# FubarStep_v13.net
KiCad netlist of a schematic drawn in EAGLE
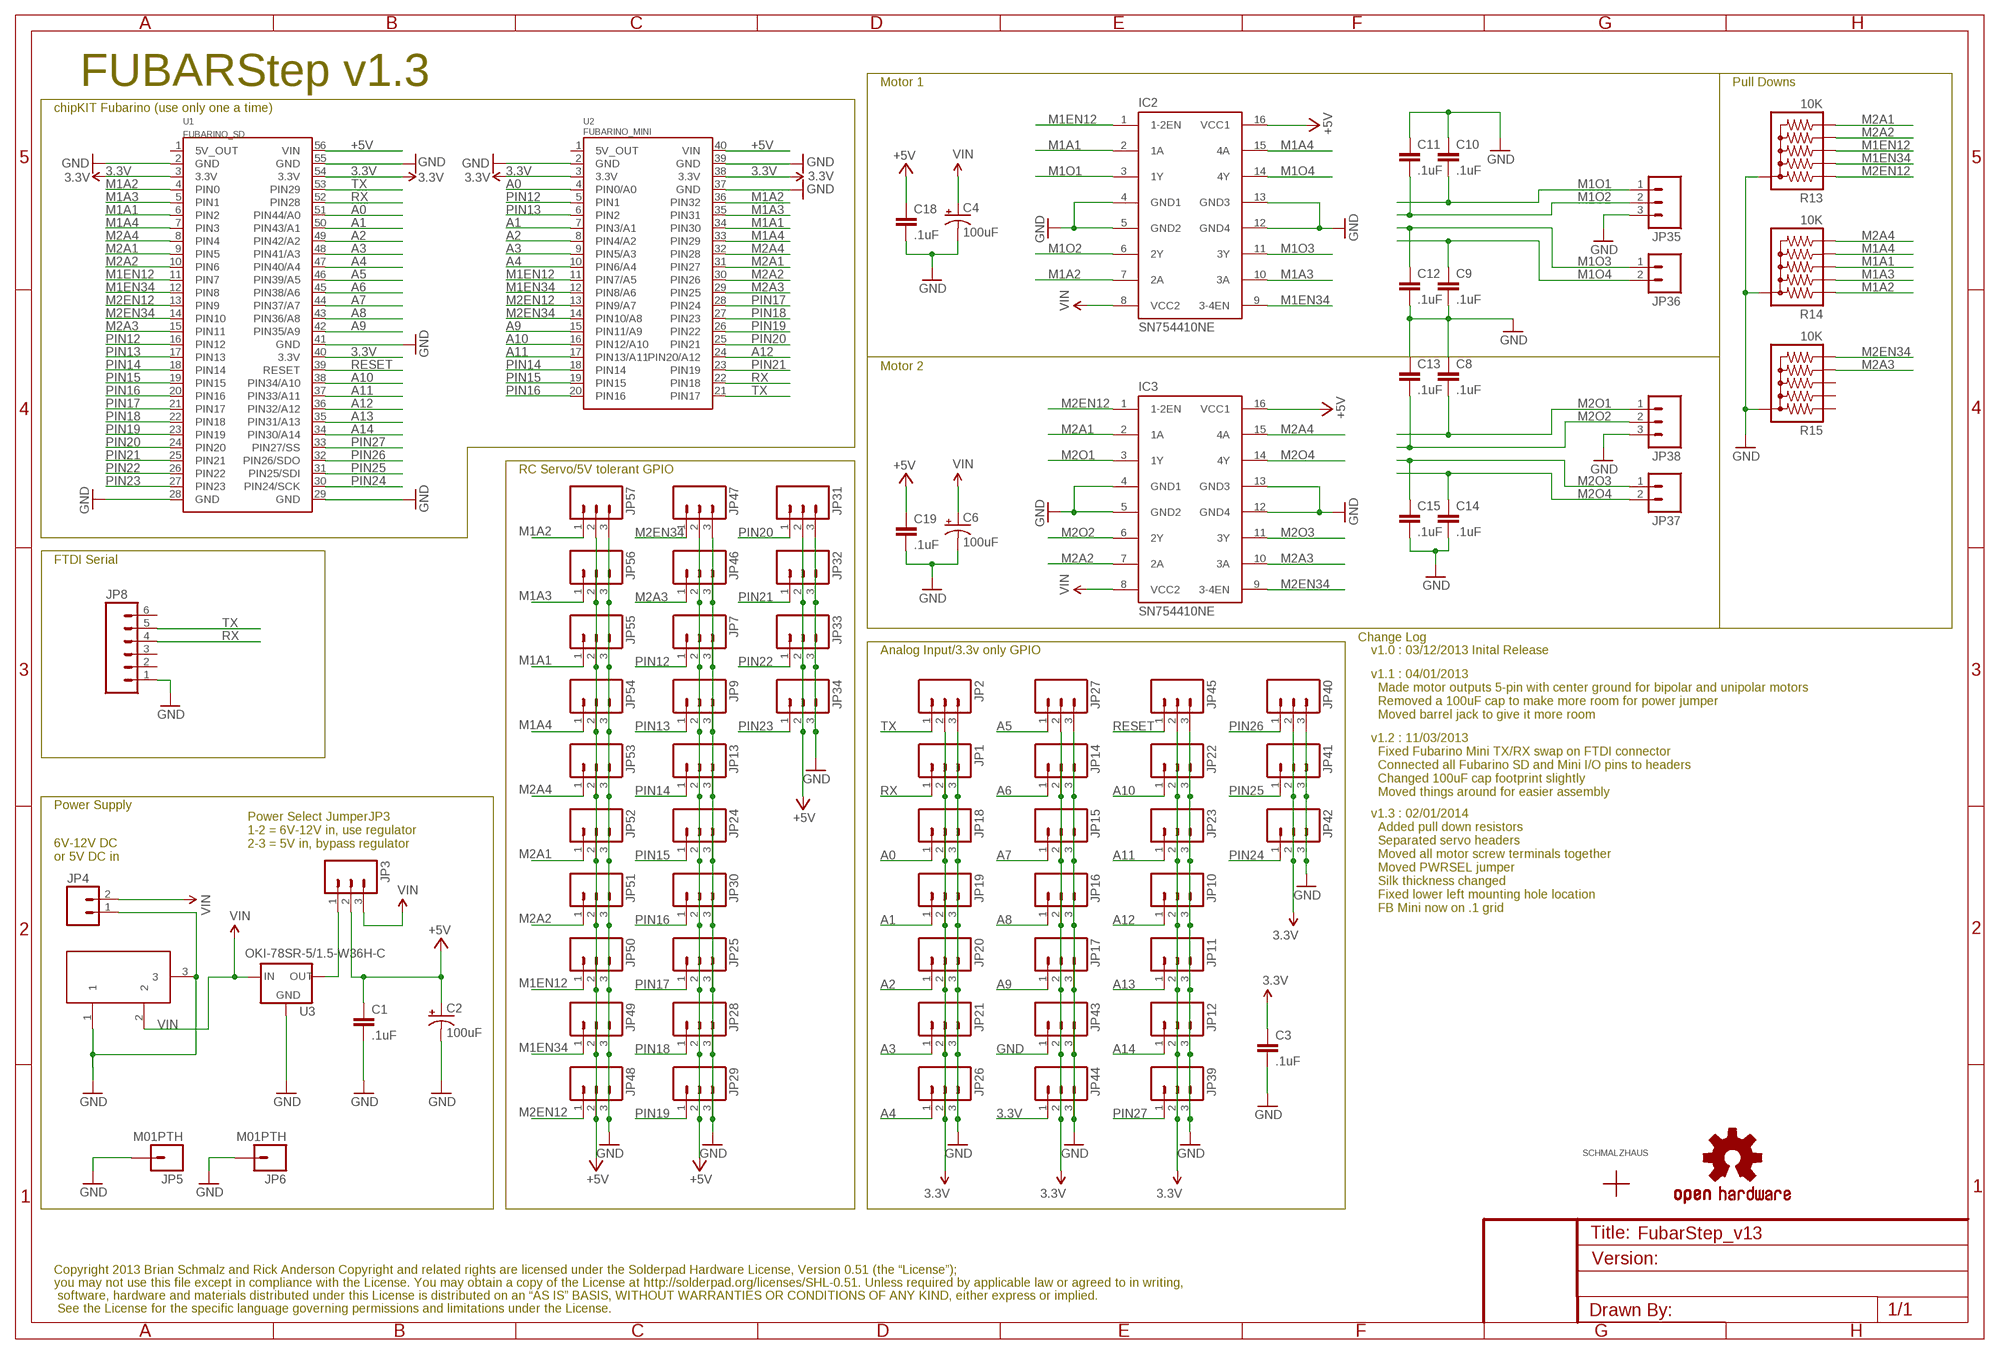
[diagram p0: schematic, sheet 1]

(export (version "E")
  (design (tool "Eeschema 10.0.6"))
  (components
    (comp (ref "C1")
      (value ".1uF")
      (footprint "eagle-import:CAP-PTH-SMALL")
      (libsource (lib "eagle-import") (part "CAPPTH"))
    )
    (comp (ref "C2")
      (value "100uF")
      (footprint "eagle-import:CPOL-RADIAL-100UF")
      (libsource (lib "eagle-import") (part "CAP_ELECTROLYTICPTH1_BPS"))
    )
    (comp (ref "C3")
      (value ".1uF")
      (footprint "eagle-import:CAP-PTH-SMALL")
      (libsource (lib "eagle-import") (part "CAPPTH"))
    )
    (comp (ref "C4")
      (value "100uF")
      (footprint "eagle-import:CPOL-RADIAL-100UF")
      (libsource (lib "eagle-import") (part "CAP_ELECTROLYTICPTH1_BPS"))
    )
    (comp (ref "C6")
      (value "100uF")
      (footprint "eagle-import:CPOL-RADIAL-100UF")
      (libsource (lib "eagle-import") (part "CAP_ELECTROLYTICPTH1_BPS"))
    )
    (comp (ref "C8")
      (value ".1uF")
      (footprint "eagle-import:CAP-PTH-SMALL")
      (libsource (lib "eagle-import") (part "CAPPTH"))
    )
    (comp (ref "C9")
      (value ".1uF")
      (footprint "eagle-import:CAP-PTH-SMALL")
      (libsource (lib "eagle-import") (part "CAPPTH"))
    )
    (comp (ref "C10")
      (value ".1uF")
      (footprint "eagle-import:CAP-PTH-SMALL")
      (libsource (lib "eagle-import") (part "CAPPTH"))
    )
    (comp (ref "C11")
      (value ".1uF")
      (footprint "eagle-import:CAP-PTH-SMALL")
      (libsource (lib "eagle-import") (part "CAPPTH"))
    )
    (comp (ref "C12")
      (value ".1uF")
      (footprint "eagle-import:CAP-PTH-SMALL")
      (libsource (lib "eagle-import") (part "CAPPTH"))
    )
    (comp (ref "C13")
      (value ".1uF")
      (footprint "eagle-import:CAP-PTH-SMALL")
      (libsource (lib "eagle-import") (part "CAPPTH"))
    )
    (comp (ref "C14")
      (value ".1uF")
      (footprint "eagle-import:CAP-PTH-SMALL")
      (libsource (lib "eagle-import") (part "CAPPTH"))
    )
    (comp (ref "C15")
      (value ".1uF")
      (footprint "eagle-import:CAP-PTH-SMALL")
      (libsource (lib "eagle-import") (part "CAPPTH"))
    )
    (comp (ref "C18")
      (value ".1uF")
      (footprint "eagle-import:CAP-PTH-SMALL")
      (libsource (lib "eagle-import") (part "CAPPTH"))
    )
    (comp (ref "C19")
      (value ".1uF")
      (footprint "eagle-import:CAP-PTH-SMALL")
      (libsource (lib "eagle-import") (part "CAPPTH"))
    )
    (comp (ref "IC2")
      (value "SN754410NE")
      (footprint "eagle-import:DIL16")
      (fields (field (name "MF") "Arrow Electronics") (field (name "MPN") "L293E"))
      (libsource (lib "eagle-import") (part "L293E"))
    )
    (comp (ref "IC3")
      (value "SN754410NE")
      (footprint "eagle-import:DIL16")
      (fields (field (name "MF") "Arrow Electronics") (field (name "MPN") "L293E"))
      (libsource (lib "eagle-import") (part "L293E"))
    )
    (comp (ref "JP1")
      (value "M03PTH")
      (footprint "eagle-import:1X03")
      (libsource (lib "eagle-import") (part "M03PTH"))
    )
    (comp (ref "JP2")
      (value "M03PTH")
      (footprint "eagle-import:1X03")
      (libsource (lib "eagle-import") (part "M03PTH"))
    )
    (comp (ref "JP3")
      (value "M03PTH")
      (footprint "eagle-import:1X03")
      (libsource (lib "eagle-import") (part "M03PTH"))
    )
    (comp (ref "JP4")
      (value "M023.5MM")
      (footprint "eagle-import:SCREWTERMINAL-3.5MM-2")
      (libsource (lib "eagle-import") (part "M023.5MM"))
    )
    (comp (ref "JP5")
      (value "M01PTH")
      (footprint "eagle-import:1X01")
      (libsource (lib "eagle-import") (part "M01PTH"))
    )
    (comp (ref "JP6")
      (value "M01PTH")
      (footprint "eagle-import:1X01")
      (libsource (lib "eagle-import") (part "M01PTH"))
    )
    (comp (ref "JP7")
      (value "M03PTH")
      (footprint "eagle-import:1X03")
      (libsource (lib "eagle-import") (part "M03PTH"))
    )
    (comp (ref "JP8")
      (value "M06LOCK")
      (footprint "eagle-import:1X06_LOCK")
      (libsource (lib "eagle-import") (part "M06LOCK"))
    )
    (comp (ref "JP9")
      (value "M03PTH")
      (footprint "eagle-import:1X03")
      (libsource (lib "eagle-import") (part "M03PTH"))
    )
    (comp (ref "JP10")
      (value "M03PTH")
      (footprint "eagle-import:1X03")
      (libsource (lib "eagle-import") (part "M03PTH"))
    )
    (comp (ref "JP11")
      (value "M03PTH")
      (footprint "eagle-import:1X03")
      (libsource (lib "eagle-import") (part "M03PTH"))
    )
    (comp (ref "JP12")
      (value "M03PTH")
      (footprint "eagle-import:1X03")
      (libsource (lib "eagle-import") (part "M03PTH"))
    )
    (comp (ref "JP13")
      (value "M03PTH")
      (footprint "eagle-import:1X03")
      (libsource (lib "eagle-import") (part "M03PTH"))
    )
    (comp (ref "JP14")
      (value "M03PTH")
      (footprint "eagle-import:1X03")
      (libsource (lib "eagle-import") (part "M03PTH"))
    )
    (comp (ref "JP15")
      (value "M03PTH")
      (footprint "eagle-import:1X03")
      (libsource (lib "eagle-import") (part "M03PTH"))
    )
    (comp (ref "JP16")
      (value "M03PTH")
      (footprint "eagle-import:1X03")
      (libsource (lib "eagle-import") (part "M03PTH"))
    )
    (comp (ref "JP17")
      (value "M03PTH")
      (footprint "eagle-import:1X03")
      (libsource (lib "eagle-import") (part "M03PTH"))
    )
    (comp (ref "JP18")
      (value "M03PTH")
      (footprint "eagle-import:1X03")
      (libsource (lib "eagle-import") (part "M03PTH"))
    )
    (comp (ref "JP19")
      (value "M03PTH")
      (footprint "eagle-import:1X03")
      (libsource (lib "eagle-import") (part "M03PTH"))
    )
    (comp (ref "JP20")
      (value "M03PTH")
      (footprint "eagle-import:1X03")
      (libsource (lib "eagle-import") (part "M03PTH"))
    )
    (comp (ref "JP21")
      (value "M03PTH")
      (footprint "eagle-import:1X03")
      (libsource (lib "eagle-import") (part "M03PTH"))
    )
    (comp (ref "JP22")
      (value "M03PTH")
      (footprint "eagle-import:1X03")
      (libsource (lib "eagle-import") (part "M03PTH"))
    )
    (comp (ref "JP23")
      (value "M03PTH")
      (footprint "eagle-import:1X03")
      (libsource (lib "eagle-import") (part "M03PTH"))
    )
    (comp (ref "JP24")
      (value "M03PTH")
      (footprint "eagle-import:1X03")
      (libsource (lib "eagle-import") (part "M03PTH"))
    )
    (comp (ref "JP25")
      (value "M03PTH")
      (footprint "eagle-import:1X03")
      (libsource (lib "eagle-import") (part "M03PTH"))
    )
    (comp (ref "JP26")
      (value "M03PTH")
      (footprint "eagle-import:1X03")
      (libsource (lib "eagle-import") (part "M03PTH"))
    )
    (comp (ref "JP27")
      (value "M03PTH")
      (footprint "eagle-import:1X03")
      (libsource (lib "eagle-import") (part "M03PTH"))
    )
    (comp (ref "JP28")
      (value "M03PTH")
      (footprint "eagle-import:1X03")
      (libsource (lib "eagle-import") (part "M03PTH"))
    )
    (comp (ref "JP29")
      (value "M03PTH")
      (footprint "eagle-import:1X03")
      (libsource (lib "eagle-import") (part "M03PTH"))
    )
    (comp (ref "JP30")
      (value "M03PTH")
      (footprint "eagle-import:1X03")
      (libsource (lib "eagle-import") (part "M03PTH"))
    )
    (comp (ref "JP31")
      (value "M03PTH")
      (footprint "eagle-import:1X03")
      (libsource (lib "eagle-import") (part "M03PTH"))
    )
    (comp (ref "JP32")
      (value "M03PTH")
      (footprint "eagle-import:1X03")
      (libsource (lib "eagle-import") (part "M03PTH"))
    )
    (comp (ref "JP33")
      (value "M03PTH")
      (footprint "eagle-import:1X03")
      (libsource (lib "eagle-import") (part "M03PTH"))
    )
    (comp (ref "JP34")
      (value "M03PTH")
      (footprint "eagle-import:1X03")
      (libsource (lib "eagle-import") (part "M03PTH"))
    )
    (comp (ref "JP35")
      (value "M03SCREW")
      (footprint "eagle-import:SCREWTERMINAL-3.5MM-3")
      (libsource (lib "eagle-import") (part "M03SCREW"))
    )
    (comp (ref "JP36")
      (value "M023.5MM")
      (footprint "eagle-import:SCREWTERMINAL-3.5MM-2")
      (libsource (lib "eagle-import") (part "M023.5MM"))
    )
    (comp (ref "JP37")
      (value "M023.5MM")
      (footprint "eagle-import:SCREWTERMINAL-3.5MM-2")
      (libsource (lib "eagle-import") (part "M023.5MM"))
    )
    (comp (ref "JP38")
      (value "M03SCREW")
      (footprint "eagle-import:SCREWTERMINAL-3.5MM-3")
      (libsource (lib "eagle-import") (part "M03SCREW"))
    )
    (comp (ref "JP39")
      (value "M03PTH")
      (footprint "eagle-import:1X03")
      (libsource (lib "eagle-import") (part "M03PTH"))
    )
    (comp (ref "JP40")
      (value "M03PTH")
      (footprint "eagle-import:1X03")
      (libsource (lib "eagle-import") (part "M03PTH"))
    )
    (comp (ref "JP41")
      (value "M03PTH")
      (footprint "eagle-import:1X03")
      (libsource (lib "eagle-import") (part "M03PTH"))
    )
    (comp (ref "JP42")
      (value "M03PTH")
      (footprint "eagle-import:1X03")
      (libsource (lib "eagle-import") (part "M03PTH"))
    )
    (comp (ref "JP43")
      (value "M03PTH")
      (footprint "eagle-import:1X03")
      (libsource (lib "eagle-import") (part "M03PTH"))
    )
    (comp (ref "JP44")
      (value "M03PTH")
      (footprint "eagle-import:1X03")
      (libsource (lib "eagle-import") (part "M03PTH"))
    )
    (comp (ref "JP45")
      (value "M03PTH")
      (footprint "eagle-import:1X03")
      (libsource (lib "eagle-import") (part "M03PTH"))
    )
    (comp (ref "JP46")
      (value "M03PTH")
      (footprint "eagle-import:1X03")
      (libsource (lib "eagle-import") (part "M03PTH"))
    )
    (comp (ref "JP47")
      (value "M03PTH")
      (footprint "eagle-import:1X03")
      (libsource (lib "eagle-import") (part "M03PTH"))
    )
    (comp (ref "JP48")
      (value "M03PTH")
      (footprint "eagle-import:1X03")
      (libsource (lib "eagle-import") (part "M03PTH"))
    )
    (comp (ref "JP49")
      (value "M03PTH")
      (footprint "eagle-import:1X03")
      (libsource (lib "eagle-import") (part "M03PTH"))
    )
    (comp (ref "JP50")
      (value "M03PTH")
      (footprint "eagle-import:1X03")
      (libsource (lib "eagle-import") (part "M03PTH"))
    )
    (comp (ref "JP51")
      (value "M03PTH")
      (footprint "eagle-import:1X03")
      (libsource (lib "eagle-import") (part "M03PTH"))
    )
    (comp (ref "JP52")
      (value "M03PTH")
      (footprint "eagle-import:1X03")
      (libsource (lib "eagle-import") (part "M03PTH"))
    )
    (comp (ref "JP53")
      (value "M03PTH")
      (footprint "eagle-import:1X03")
      (libsource (lib "eagle-import") (part "M03PTH"))
    )
    (comp (ref "JP54")
      (value "M03PTH")
      (footprint "eagle-import:1X03")
      (libsource (lib "eagle-import") (part "M03PTH"))
    )
    (comp (ref "JP55")
      (value "M03PTH")
      (footprint "eagle-import:1X03")
      (libsource (lib "eagle-import") (part "M03PTH"))
    )
    (comp (ref "JP56")
      (value "M03PTH")
      (footprint "eagle-import:1X03")
      (libsource (lib "eagle-import") (part "M03PTH"))
    )
    (comp (ref "JP57")
      (value "M03PTH")
      (footprint "eagle-import:1X03")
      (libsource (lib "eagle-import") (part "M03PTH"))
    )
    (comp (ref "LOGO1")
      (value "OSHW-LOGOM")
      (footprint "eagle-import:OSHW-LOGO-M")
      (libsource (lib "eagle-import") (part "OSHW-LOGOM"))
    )
    (comp (ref "R13")
      (value "10K")
      (footprint "eagle-import:RPACK-SIP-PTH-5")
      (libsource (lib "eagle-import") (part "RPACK-BUSSED-SIP-PTH-5"))
    )
    (comp (ref "R14")
      (value "10K")
      (footprint "eagle-import:RPACK-SIP-PTH-5")
      (libsource (lib "eagle-import") (part "RPACK-BUSSED-SIP-PTH-5"))
    )
    (comp (ref "R15")
      (value "10K")
      (footprint "eagle-import:RPACK-SIP-PTH-5")
      (libsource (lib "eagle-import") (part "RPACK-BUSSED-SIP-PTH-5"))
    )
    (comp (ref "U$1")
      (value "SCHMALZHAUSSCHMALZHAUS_SMALL")
      (footprint "eagle-import:SCHMALZHAUS_SMALL")
      (libsource (lib "eagle-import") (part "SCHMALZHAUSSCHMALZHAUS_SMALL"))
    )
    (comp (ref "U1")
      (value "FUBARINO_SD")
      (footprint "eagle-import:FUBARINO_SD")
      (libsource (lib "eagle-import") (part "FUBARINO_SD"))
    )
    (comp (ref "U2")
      (value "FUBARINO_MINI")
      (footprint "eagle-import:FUBARINO_MINI")
      (libsource (lib "eagle-import") (part "FUBARINO_MINI"))
    )
    (comp (ref "U3")
      (value "OKI-78SR-5/1.5-W36H-C")
      (footprint "eagle-import:TO220-IGO")
      (libsource (lib "eagle-import") (part "V_REG_78XXSINK"))
    )
    (comp (ref "X1")
      (value "DC21MMX")
      (footprint "eagle-import:DC-21MM")
      (libsource (lib "eagle-import") (part "DC21MMX"))
    )
  )
  (nets
    (net (code "1") (name "+5V") (class "Default")
      (node (ref "C1") (pin "1") (pinfunction "1_1") (pintype "passive"))
      (node (ref "C18") (pin "1") (pinfunction "1_1") (pintype "passive"))
      (node (ref "C19") (pin "1") (pinfunction "1_1") (pintype "passive"))
      (node (ref "C2") (pin "1") (pinfunction "+_1") (pintype "passive"))
      (node (ref "IC2") (pin "16") (pinfunction "VCC1_16") (pintype "power_in"))
      (node (ref "IC3") (pin "16") (pinfunction "VCC1_16") (pintype "power_in"))
      (node (ref "JP13") (pin "2") (pinfunction "2_2") (pintype "passive"))
      (node (ref "JP24") (pin "2") (pinfunction "2_2") (pintype "passive"))
      (node (ref "JP25") (pin "2") (pinfunction "2_2") (pintype "passive"))
      (node (ref "JP28") (pin "2") (pinfunction "2_2") (pintype "passive"))
      (node (ref "JP29") (pin "2") (pinfunction "2_2") (pintype "passive"))
      (node (ref "JP3") (pin "2") (pinfunction "2_2") (pintype "passive"))
      (node (ref "JP30") (pin "2") (pinfunction "2_2") (pintype "passive"))
      (node (ref "JP31") (pin "2") (pinfunction "2_2") (pintype "passive"))
      (node (ref "JP32") (pin "2") (pinfunction "2_2") (pintype "passive"))
      (node (ref "JP33") (pin "2") (pinfunction "2_2") (pintype "passive"))
      (node (ref "JP34") (pin "2") (pinfunction "2_2") (pintype "passive"))
      (node (ref "JP46") (pin "2") (pinfunction "2_2") (pintype "passive"))
      (node (ref "JP47") (pin "2") (pinfunction "2_2") (pintype "passive"))
      (node (ref "JP48") (pin "2") (pinfunction "2_2") (pintype "passive"))
      (node (ref "JP49") (pin "2") (pinfunction "2_2") (pintype "passive"))
      (node (ref "JP50") (pin "2") (pinfunction "2_2") (pintype "passive"))
      (node (ref "JP51") (pin "2") (pinfunction "2_2") (pintype "passive"))
      (node (ref "JP52") (pin "2") (pinfunction "2_2") (pintype "passive"))
      (node (ref "JP53") (pin "2") (pinfunction "2_2") (pintype "passive"))
      (node (ref "JP54") (pin "2") (pinfunction "2_2") (pintype "passive"))
      (node (ref "JP55") (pin "2") (pinfunction "2_2") (pintype "passive"))
      (node (ref "JP56") (pin "2") (pinfunction "2_2") (pintype "passive"))
      (node (ref "JP57") (pin "2") (pinfunction "2_2") (pintype "passive"))
      (node (ref "JP7") (pin "2") (pinfunction "2_2") (pintype "passive"))
      (node (ref "JP9") (pin "2") (pinfunction "2_2") (pintype "passive"))
      (node (ref "U1") (pin "56") (pinfunction "VIN_56") (pintype "bidirectional"))
      (node (ref "U2") (pin "40") (pinfunction "VIN_40") (pintype "bidirectional"))
    )
    (net (code "2") (name "/A0") (class "Default")
      (node (ref "JP18") (pin "1") (pinfunction "1_1") (pintype "passive"))
      (node (ref "U1") (pin "51") (pinfunction "PIN44/A0_51") (pintype "bidirectional"))
      (node (ref "U2") (pin "4") (pinfunction "PIN0/A0_4") (pintype "bidirectional"))
    )
    (net (code "3") (name "/A1") (class "Default")
      (node (ref "JP19") (pin "1") (pinfunction "1_1") (pintype "passive"))
      (node (ref "U1") (pin "50") (pinfunction "PIN43/A1_50") (pintype "bidirectional"))
      (node (ref "U2") (pin "7") (pinfunction "PIN3/A1_7") (pintype "bidirectional"))
    )
    (net (code "4") (name "/A2") (class "Default")
      (node (ref "JP20") (pin "1") (pinfunction "1_1") (pintype "passive"))
      (node (ref "U1") (pin "49") (pinfunction "PIN42/A2_49") (pintype "bidirectional"))
      (node (ref "U2") (pin "8") (pinfunction "PIN4/A2_8") (pintype "bidirectional"))
    )
    (net (code "5") (name "/A3") (class "Default")
      (node (ref "JP21") (pin "1") (pinfunction "1_1") (pintype "passive"))
      (node (ref "U1") (pin "48") (pinfunction "PIN41/A3_48") (pintype "bidirectional"))
      (node (ref "U2") (pin "9") (pinfunction "PIN5/A3_9") (pintype "bidirectional"))
    )
    (net (code "6") (name "/A4") (class "Default")
      (node (ref "JP26") (pin "1") (pinfunction "1_1") (pintype "passive"))
      (node (ref "U1") (pin "47") (pinfunction "PIN40/A4_47") (pintype "bidirectional"))
      (node (ref "U2") (pin "10") (pinfunction "PIN6/A4_10") (pintype "bidirectional"))
    )
    (net (code "7") (name "/A5") (class "Default")
      (node (ref "JP27") (pin "1") (pinfunction "1_1") (pintype "passive"))
      (node (ref "U1") (pin "46") (pinfunction "PIN39/A5_46") (pintype "bidirectional"))
    )
    (net (code "8") (name "/A6") (class "Default")
      (node (ref "JP14") (pin "1") (pinfunction "1_1") (pintype "passive"))
      (node (ref "U1") (pin "45") (pinfunction "PIN38/A6_45") (pintype "bidirectional"))
    )
    (net (code "9") (name "/A7") (class "Default")
      (node (ref "JP15") (pin "1") (pinfunction "1_1") (pintype "passive"))
      (node (ref "U1") (pin "44") (pinfunction "PIN37/A7_44") (pintype "bidirectional"))
    )
    (net (code "10") (name "/A8") (class "Default")
      (node (ref "JP16") (pin "1") (pinfunction "1_1") (pintype "passive"))
      (node (ref "U1") (pin "43") (pinfunction "PIN36/A8_43") (pintype "bidirectional"))
    )
    (net (code "11") (name "/A9") (class "Default")
      (node (ref "JP17") (pin "1") (pinfunction "1_1") (pintype "passive"))
      (node (ref "U1") (pin "42") (pinfunction "PIN35/A9_42") (pintype "bidirectional"))
      (node (ref "U2") (pin "15") (pinfunction "PIN11/A9_15") (pintype "bidirectional"))
    )
    (net (code "12") (name "/A10") (class "Default")
      (node (ref "JP22") (pin "1") (pinfunction "1_1") (pintype "passive"))
      (node (ref "U1") (pin "38") (pinfunction "PIN34/A10_38") (pintype "bidirectional"))
      (node (ref "U2") (pin "16") (pinfunction "PIN12/A10_16") (pintype "bidirectional"))
    )
    (net (code "13") (name "/A11") (class "Default")
      (node (ref "JP23") (pin "1") (pinfunction "1_1") (pintype "passive"))
      (node (ref "U1") (pin "37") (pinfunction "PIN33/A11_37") (pintype "bidirectional"))
      (node (ref "U2") (pin "17") (pinfunction "PIN13/A11_17") (pintype "bidirectional"))
    )
    (net (code "14") (name "/A12") (class "Default")
      (node (ref "JP10") (pin "1") (pinfunction "1_1") (pintype "passive"))
      (node (ref "U1") (pin "36") (pinfunction "PIN32/A12_36") (pintype "bidirectional"))
      (node (ref "U2") (pin "24") (pinfunction "PIN20/A12_24") (pintype "bidirectional"))
    )
    (net (code "15") (name "/A13") (class "Default")
      (node (ref "JP11") (pin "1") (pinfunction "1_1") (pintype "passive"))
      (node (ref "U1") (pin "35") (pinfunction "PIN31/A13_35") (pintype "bidirectional"))
    )
    (net (code "16") (name "/A14") (class "Default")
      (node (ref "JP12") (pin "1") (pinfunction "1_1") (pintype "passive"))
      (node (ref "U1") (pin "34") (pinfunction "PIN30/A14_34") (pintype "bidirectional"))
    )
    (net (code "17") (name "/M1A1") (class "Default")
      (node (ref "IC2") (pin "2") (pinfunction "1A_2") (pintype "input"))
      (node (ref "JP55") (pin "1") (pinfunction "1_1") (pintype "passive"))
      (node (ref "R14") (pin "P$4") (pinfunction "4_P$4") (pintype "passive"))
      (node (ref "U1") (pin "6") (pinfunction "PIN2_6") (pintype "bidirectional"))
      (node (ref "U2") (pin "34") (pinfunction "PIN30_34") (pintype "bidirectional"))
    )
    (net (code "18") (name "/M1A2") (class "Default")
      (node (ref "IC2") (pin "7") (pinfunction "2A_7") (pintype "input"))
      (node (ref "JP57") (pin "1") (pinfunction "1_1") (pintype "passive"))
      (node (ref "R14") (pin "P$2") (pinfunction "2_P$2") (pintype "passive"))
      (node (ref "U1") (pin "4") (pinfunction "PIN0_4") (pintype "bidirectional"))
      (node (ref "U2") (pin "36") (pinfunction "PIN32_36") (pintype "bidirectional"))
    )
    (net (code "19") (name "/M1A3") (class "Default")
      (node (ref "IC2") (pin "10") (pinfunction "3A_10") (pintype "input"))
      (node (ref "JP56") (pin "1") (pinfunction "1_1") (pintype "passive"))
      (node (ref "R14") (pin "P$3") (pinfunction "3_P$3") (pintype "passive"))
      (node (ref "U1") (pin "5") (pinfunction "PIN1_5") (pintype "bidirectional"))
      (node (ref "U2") (pin "35") (pinfunction "PIN31_35") (pintype "bidirectional"))
    )
    (net (code "20") (name "/M1A4") (class "Default")
      (node (ref "IC2") (pin "15") (pinfunction "4A_15") (pintype "input"))
      (node (ref "JP54") (pin "1") (pinfunction "1_1") (pintype "passive"))
      (node (ref "R14") (pin "P$5") (pinfunction "5_P$5") (pintype "passive"))
      (node (ref "U1") (pin "7") (pinfunction "PIN3_7") (pintype "bidirectional"))
      (node (ref "U2") (pin "33") (pinfunction "PIN29_33") (pintype "bidirectional"))
    )
    (net (code "21") (name "/M1EN12") (class "Default")
      (node (ref "IC2") (pin "1") (pinfunction "1-2EN_1") (pintype "input"))
      (node (ref "JP50") (pin "1") (pinfunction "1_1") (pintype "passive"))
      (node (ref "R13") (pin "P$4") (pinfunction "4_P$4") (pintype "passive"))
      (node (ref "U1") (pin "11") (pinfunction "PIN7_11") (pintype "bidirectional"))
      (node (ref "U2") (pin "11") (pinfunction "PIN7/A5_11") (pintype "bidirectional"))
    )
    (net (code "22") (name "/M1EN34") (class "Default")
      (node (ref "IC2") (pin "9") (pinfunction "3-4EN_9") (pintype "input"))
      (node (ref "JP49") (pin "1") (pinfunction "1_1") (pintype "passive"))
      (node (ref "R13") (pin "P$3") (pinfunction "3_P$3") (pintype "passive"))
      (node (ref "U1") (pin "12") (pinfunction "PIN8_12") (pintype "bidirectional"))
      (node (ref "U2") (pin "12") (pinfunction "PIN8/A6_12") (pintype "bidirectional"))
    )
    (net (code "23") (name "/M1O1") (class "Default")
      (node (ref "C10") (pin "2") (pinfunction "2_2") (pintype "passive"))
      (node (ref "IC2") (pin "3") (pinfunction "1Y_3") (pintype "output"))
      (node (ref "JP35") (pin "1") (pinfunction "1_1") (pintype "passive"))
    )
    (net (code "24") (name "/M1O2") (class "Default")
      (node (ref "C11") (pin "2") (pinfunction "2_2") (pintype "passive"))
      (node (ref "IC2") (pin "6") (pinfunction "2Y_6") (pintype "output"))
      (node (ref "JP35") (pin "2") (pinfunction "2_2") (pintype "passive"))
    )
    (net (code "25") (name "/M1O3") (class "Default")
      (node (ref "C12") (pin "1") (pinfunction "1_1") (pintype "passive"))
      (node (ref "IC2") (pin "11") (pinfunction "3Y_11") (pintype "output"))
      (node (ref "JP36") (pin "1") (pinfunction "1_1") (pintype "passive"))
    )
    (net (code "26") (name "/M1O4") (class "Default")
      (node (ref "C9") (pin "1") (pinfunction "1_1") (pintype "passive"))
      (node (ref "IC2") (pin "14") (pinfunction "4Y_14") (pintype "output"))
      (node (ref "JP36") (pin "2") (pinfunction "2_2") (pintype "passive"))
    )
    (net (code "27") (name "/M2A1") (class "Default")
      (node (ref "IC3") (pin "2") (pinfunction "1A_2") (pintype "input"))
      (node (ref "JP52") (pin "1") (pinfunction "1_1") (pintype "passive"))
      (node (ref "R13") (pin "P$6") (pinfunction "6_P$6") (pintype "passive"))
      (node (ref "U1") (pin "9") (pinfunction "PIN5_9") (pintype "bidirectional"))
      (node (ref "U2") (pin "31") (pinfunction "PIN27_31") (pintype "bidirectional"))
    )
    (net (code "28") (name "/M2A2") (class "Default")
      (node (ref "IC3") (pin "7") (pinfunction "2A_7") (pintype "input"))
      (node (ref "JP51") (pin "1") (pinfunction "1_1") (pintype "passive"))
      (node (ref "R13") (pin "P$5") (pinfunction "5_P$5") (pintype "passive"))
      (node (ref "U1") (pin "10") (pinfunction "PIN6_10") (pintype "bidirectional"))
      (node (ref "U2") (pin "30") (pinfunction "PIN26_30") (pintype "bidirectional"))
    )
    (net (code "29") (name "/M2A3") (class "Default")
      (node (ref "IC3") (pin "10") (pinfunction "3A_10") (pintype "input"))
      (node (ref "JP46") (pin "1") (pinfunction "1_1") (pintype "passive"))
      (node (ref "R15") (pin "P$5") (pinfunction "5_P$5") (pintype "passive"))
      (node (ref "U1") (pin "15") (pinfunction "PIN11_15") (pintype "bidirectional"))
      (node (ref "U2") (pin "29") (pinfunction "PIN25_29") (pintype "bidirectional"))
    )
    (net (code "30") (name "/M2A4") (class "Default")
      (node (ref "IC3") (pin "15") (pinfunction "4A_15") (pintype "input"))
      (node (ref "JP53") (pin "1") (pinfunction "1_1") (pintype "passive"))
      (node (ref "R14") (pin "P$6") (pinfunction "6_P$6") (pintype "passive"))
      (node (ref "U1") (pin "8") (pinfunction "PIN4_8") (pintype "bidirectional"))
      (node (ref "U2") (pin "32") (pinfunction "PIN28_32") (pintype "bidirectional"))
    )
    (net (code "31") (name "/M2EN12") (class "Default")
      (node (ref "IC3") (pin "1") (pinfunction "1-2EN_1") (pintype "input"))
      (node (ref "JP48") (pin "1") (pinfunction "1_1") (pintype "passive"))
      (node (ref "R13") (pin "P$2") (pinfunction "2_P$2") (pintype "passive"))
      (node (ref "U1") (pin "13") (pinfunction "PIN9_13") (pintype "bidirectional"))
      (node (ref "U2") (pin "13") (pinfunction "PIN9/A7_13") (pintype "bidirectional"))
    )
    (net (code "32") (name "/M2EN34") (class "Default")
      (node (ref "IC3") (pin "9") (pinfunction "3-4EN_9") (pintype "input"))
      (node (ref "JP47") (pin "1") (pinfunction "1_1") (pintype "passive"))
      (node (ref "R15") (pin "P$6") (pinfunction "6_P$6") (pintype "passive"))
      (node (ref "U1") (pin "14") (pinfunction "PIN10_14") (pintype "bidirectional"))
      (node (ref "U2") (pin "14") (pinfunction "PIN10/A8_14") (pintype "bidirectional"))
    )
    (net (code "33") (name "/M2O1") (class "Default")
      (node (ref "C8") (pin "2") (pinfunction "2_2") (pintype "passive"))
      (node (ref "IC3") (pin "3") (pinfunction "1Y_3") (pintype "output"))
      (node (ref "JP38") (pin "1") (pinfunction "1_1") (pintype "passive"))
    )
    (net (code "34") (name "/M2O2") (class "Default")
      (node (ref "C13") (pin "2") (pinfunction "2_2") (pintype "passive"))
      (node (ref "IC3") (pin "6") (pinfunction "2Y_6") (pintype "output"))
      (node (ref "JP38") (pin "2") (pinfunction "2_2") (pintype "passive"))
    )
    (net (code "35") (name "/M2O3") (class "Default")
      (node (ref "C15") (pin "1") (pinfunction "1_1") (pintype "passive"))
      (node (ref "IC3") (pin "11") (pinfunction "3Y_11") (pintype "output"))
      (node (ref "JP37") (pin "1") (pinfunction "1_1") (pintype "passive"))
    )
    (net (code "36") (name "/M2O4") (class "Default")
      (node (ref "C14") (pin "1") (pinfunction "1_1") (pintype "passive"))
      (node (ref "IC3") (pin "14") (pinfunction "4Y_14") (pintype "output"))
      (node (ref "JP37") (pin "2") (pinfunction "2_2") (pintype "passive"))
    )
    (net (code "37") (name "/PIN12") (class "Default")
      (node (ref "JP7") (pin "1") (pinfunction "1_1") (pintype "passive"))
      (node (ref "U1") (pin "16") (pinfunction "PIN12_16") (pintype "bidirectional"))
      (node (ref "U2") (pin "5") (pinfunction "PIN1_5") (pintype "bidirectional"))
    )
    (net (code "38") (name "/PIN13") (class "Default")
      (node (ref "JP9") (pin "1") (pinfunction "1_1") (pintype "passive"))
      (node (ref "U1") (pin "17") (pinfunction "PIN13_17") (pintype "bidirectional"))
      (node (ref "U2") (pin "6") (pinfunction "PIN2_6") (pintype "bidirectional"))
    )
    (net (code "39") (name "/PIN14") (class "Default")
      (node (ref "JP13") (pin "1") (pinfunction "1_1") (pintype "passive"))
      (node (ref "U1") (pin "18") (pinfunction "PIN14_18") (pintype "bidirectional"))
      (node (ref "U2") (pin "18") (pinfunction "PIN14_18") (pintype "bidirectional"))
    )
    (net (code "40") (name "/PIN15") (class "Default")
      (node (ref "JP24") (pin "1") (pinfunction "1_1") (pintype "passive"))
      (node (ref "U1") (pin "19") (pinfunction "PIN15_19") (pintype "bidirectional"))
      (node (ref "U2") (pin "19") (pinfunction "PIN15_19") (pintype "bidirectional"))
    )
    (net (code "41") (name "/PIN16") (class "Default")
      (node (ref "JP30") (pin "1") (pinfunction "1_1") (pintype "passive"))
      (node (ref "U1") (pin "20") (pinfunction "PIN16_20") (pintype "bidirectional"))
      (node (ref "U2") (pin "20") (pinfunction "PIN16_20") (pintype "bidirectional"))
    )
    (net (code "42") (name "/PIN17") (class "Default")
      (node (ref "JP25") (pin "1") (pinfunction "1_1") (pintype "passive"))
      (node (ref "U1") (pin "21") (pinfunction "PIN17_21") (pintype "bidirectional"))
      (node (ref "U2") (pin "28") (pinfunction "PIN24_28") (pintype "bidirectional"))
    )
    (net (code "43") (name "/PIN18") (class "Default")
      (node (ref "JP28") (pin "1") (pinfunction "1_1") (pintype "passive"))
      (node (ref "U1") (pin "22") (pinfunction "PIN18_22") (pintype "bidirectional"))
      (node (ref "U2") (pin "27") (pinfunction "PIN23_27") (pintype "bidirectional"))
    )
    (net (code "44") (name "/PIN19") (class "Default")
      (node (ref "JP29") (pin "1") (pinfunction "1_1") (pintype "passive"))
      (node (ref "U1") (pin "23") (pinfunction "PIN19_23") (pintype "bidirectional"))
      (node (ref "U2") (pin "26") (pinfunction "PIN22_26") (pintype "bidirectional"))
    )
    (net (code "45") (name "/PIN20") (class "Default")
      (node (ref "JP31") (pin "1") (pinfunction "1_1") (pintype "passive"))
      (node (ref "U1") (pin "24") (pinfunction "PIN20_24") (pintype "bidirectional"))
      (node (ref "U2") (pin "25") (pinfunction "PIN21_25") (pintype "bidirectional"))
    )
    (net (code "46") (name "/PIN21") (class "Default")
      (node (ref "JP32") (pin "1") (pinfunction "1_1") (pintype "passive"))
      (node (ref "U1") (pin "25") (pinfunction "PIN21_25") (pintype "bidirectional"))
      (node (ref "U2") (pin "23") (pinfunction "PIN19_23") (pintype "bidirectional"))
    )
    (net (code "47") (name "/PIN22") (class "Default")
      (node (ref "JP33") (pin "1") (pinfunction "1_1") (pintype "passive"))
      (node (ref "U1") (pin "26") (pinfunction "PIN22_26") (pintype "bidirectional"))
    )
    (net (code "48") (name "/PIN23") (class "Default")
      (node (ref "JP34") (pin "1") (pinfunction "1_1") (pintype "passive"))
      (node (ref "U1") (pin "27") (pinfunction "PIN23_27") (pintype "bidirectional"))
    )
    (net (code "49") (name "/PIN24") (class "Default")
      (node (ref "JP42") (pin "1") (pinfunction "1_1") (pintype "passive"))
      (node (ref "U1") (pin "30") (pinfunction "PIN24/SCK_30") (pintype "bidirectional"))
    )
    (net (code "50") (name "/PIN25") (class "Default")
      (node (ref "JP41") (pin "1") (pinfunction "1_1") (pintype "passive"))
      (node (ref "U1") (pin "31") (pinfunction "PIN25/SDI_31") (pintype "bidirectional"))
    )
    (net (code "51") (name "/PIN26") (class "Default")
      (node (ref "JP40") (pin "1") (pinfunction "1_1") (pintype "passive"))
      (node (ref "U1") (pin "32") (pinfunction "PIN26/SDO_32") (pintype "bidirectional"))
    )
    (net (code "52") (name "/PIN27") (class "Default")
      (node (ref "JP39") (pin "1") (pinfunction "1_1") (pintype "passive"))
      (node (ref "U1") (pin "33") (pinfunction "PIN27/SS_33") (pintype "bidirectional"))
    )
    (net (code "53") (name "/RESET") (class "Default")
      (node (ref "JP45") (pin "1") (pinfunction "1_1") (pintype "passive"))
      (node (ref "U1") (pin "39") (pinfunction "RESET_39") (pintype "bidirectional"))
    )
    (net (code "54") (name "/RX") (class "Default")
      (node (ref "JP1") (pin "1") (pinfunction "1_1") (pintype "passive"))
      (node (ref "JP8") (pin "4") (pinfunction "4_4") (pintype "passive"))
      (node (ref "U1") (pin "52") (pinfunction "PIN28_52") (pintype "bidirectional"))
      (node (ref "U2") (pin "22") (pinfunction "PIN18_22") (pintype "bidirectional"))
    )
    (net (code "55") (name "/TX") (class "Default")
      (node (ref "JP2") (pin "1") (pinfunction "1_1") (pintype "passive"))
      (node (ref "JP8") (pin "5") (pinfunction "5_5") (pintype "passive"))
      (node (ref "U1") (pin "53") (pinfunction "PIN29_53") (pintype "bidirectional"))
      (node (ref "U2") (pin "21") (pinfunction "PIN17_21") (pintype "bidirectional"))
    )
    (net (code "56") (name "3.3V") (class "Default")
      (node (ref "C3") (pin "1") (pinfunction "1_1") (pintype "passive"))
      (node (ref "JP1") (pin "2") (pinfunction "2_2") (pintype "passive"))
      (node (ref "JP10") (pin "2") (pinfunction "2_2") (pintype "passive"))
      (node (ref "JP11") (pin "2") (pinfunction "2_2") (pintype "passive"))
      (node (ref "JP12") (pin "2") (pinfunction "2_2") (pintype "passive"))
      (node (ref "JP14") (pin "2") (pinfunction "2_2") (pintype "passive"))
      (node (ref "JP15") (pin "2") (pinfunction "2_2") (pintype "passive"))
      (node (ref "JP16") (pin "2") (pinfunction "2_2") (pintype "passive"))
      (node (ref "JP17") (pin "2") (pinfunction "2_2") (pintype "passive"))
      (node (ref "JP18") (pin "2") (pinfunction "2_2") (pintype "passive"))
      (node (ref "JP19") (pin "2") (pinfunction "2_2") (pintype "passive"))
      (node (ref "JP2") (pin "2") (pinfunction "2_2") (pintype "passive"))
      (node (ref "JP20") (pin "2") (pinfunction "2_2") (pintype "passive"))
      (node (ref "JP21") (pin "2") (pinfunction "2_2") (pintype "passive"))
      (node (ref "JP22") (pin "2") (pinfunction "2_2") (pintype "passive"))
      (node (ref "JP23") (pin "2") (pinfunction "2_2") (pintype "passive"))
      (node (ref "JP26") (pin "2") (pinfunction "2_2") (pintype "passive"))
      (node (ref "JP27") (pin "2") (pinfunction "2_2") (pintype "passive"))
      (node (ref "JP39") (pin "2") (pinfunction "2_2") (pintype "passive"))
      (node (ref "JP40") (pin "2") (pinfunction "2_2") (pintype "passive"))
      (node (ref "JP41") (pin "2") (pinfunction "2_2") (pintype "passive"))
      (node (ref "JP42") (pin "2") (pinfunction "2_2") (pintype "passive"))
      (node (ref "JP43") (pin "2") (pinfunction "2_2") (pintype "passive"))
      (node (ref "JP44") (pin "1") (pinfunction "1_1") (pintype "passive"))
      (node (ref "JP44") (pin "2") (pinfunction "2_2") (pintype "passive"))
      (node (ref "JP45") (pin "2") (pinfunction "2_2") (pintype "passive"))
      (node (ref "U1") (pin "3") (pinfunction "3.3V_3") (pintype "bidirectional"))
      (node (ref "U1") (pin "40") (pinfunction "3.3V_40") (pintype "bidirectional"))
      (node (ref "U1") (pin "54") (pinfunction "3.3V_54") (pintype "bidirectional"))
      (node (ref "U2") (pin "3") (pinfunction "3.3V_3") (pintype "bidirectional"))
      (node (ref "U2") (pin "38") (pinfunction "3.3V_38") (pintype "bidirectional"))
    )
    (net (code "57") (name "GND") (class "Default")
      (node (ref "C1") (pin "2") (pinfunction "2_2") (pintype "passive"))
      (node (ref "C10") (pin "1") (pinfunction "1_1") (pintype "passive"))
      (node (ref "C11") (pin "1") (pinfunction "1_1") (pintype "passive"))
      (node (ref "C12") (pin "2") (pinfunction "2_2") (pintype "passive"))
      (node (ref "C13") (pin "1") (pinfunction "1_1") (pintype "passive"))
      (node (ref "C14") (pin "2") (pinfunction "2_2") (pintype "passive"))
      (node (ref "C15") (pin "2") (pinfunction "2_2") (pintype "passive"))
      (node (ref "C18") (pin "2") (pinfunction "2_2") (pintype "passive"))
      (node (ref "C19") (pin "2") (pinfunction "2_2") (pintype "passive"))
      (node (ref "C2") (pin "2") (pinfunction "-_2") (pintype "passive"))
      (node (ref "C3") (pin "2") (pinfunction "2_2") (pintype "passive"))
      (node (ref "C4") (pin "2") (pinfunction "-_2") (pintype "passive"))
      (node (ref "C6") (pin "2") (pinfunction "-_2") (pintype "passive"))
      (node (ref "C8") (pin "1") (pinfunction "1_1") (pintype "passive"))
      (node (ref "C9") (pin "2") (pinfunction "2_2") (pintype "passive"))
      (node (ref "IC2") (pin "12") (pinfunction "GND4_12") (pintype "power_in"))
      (node (ref "IC2") (pin "13") (pinfunction "GND3_13") (pintype "power_in"))
      (node (ref "IC2") (pin "4") (pinfunction "GND1_4") (pintype "power_in"))
      (node (ref "IC2") (pin "5") (pinfunction "GND2_5") (pintype "power_in"))
      (node (ref "IC3") (pin "12") (pinfunction "GND4_12") (pintype "power_in"))
      (node (ref "IC3") (pin "13") (pinfunction "GND3_13") (pintype "power_in"))
      (node (ref "IC3") (pin "4") (pinfunction "GND1_4") (pintype "power_in"))
      (node (ref "IC3") (pin "5") (pinfunction "GND2_5") (pintype "power_in"))
      (node (ref "JP1") (pin "3") (pinfunction "3_3") (pintype "passive"))
      (node (ref "JP10") (pin "3") (pinfunction "3_3") (pintype "passive"))
      (node (ref "JP11") (pin "3") (pinfunction "3_3") (pintype "passive"))
      (node (ref "JP12") (pin "3") (pinfunction "3_3") (pintype "passive"))
      (node (ref "JP13") (pin "3") (pinfunction "3_3") (pintype "passive"))
      (node (ref "JP14") (pin "3") (pinfunction "3_3") (pintype "passive"))
      (node (ref "JP15") (pin "3") (pinfunction "3_3") (pintype "passive"))
      (node (ref "JP16") (pin "3") (pinfunction "3_3") (pintype "passive"))
      (node (ref "JP17") (pin "3") (pinfunction "3_3") (pintype "passive"))
      (node (ref "JP18") (pin "3") (pinfunction "3_3") (pintype "passive"))
      (node (ref "JP19") (pin "3") (pinfunction "3_3") (pintype "passive"))
      (node (ref "JP2") (pin "3") (pinfunction "3_3") (pintype "passive"))
      (node (ref "JP20") (pin "3") (pinfunction "3_3") (pintype "passive"))
      (node (ref "JP21") (pin "3") (pinfunction "3_3") (pintype "passive"))
      (node (ref "JP22") (pin "3") (pinfunction "3_3") (pintype "passive"))
      (node (ref "JP23") (pin "3") (pinfunction "3_3") (pintype "passive"))
      (node (ref "JP24") (pin "3") (pinfunction "3_3") (pintype "passive"))
      (node (ref "JP25") (pin "3") (pinfunction "3_3") (pintype "passive"))
      (node (ref "JP26") (pin "3") (pinfunction "3_3") (pintype "passive"))
      (node (ref "JP27") (pin "3") (pinfunction "3_3") (pintype "passive"))
      (node (ref "JP28") (pin "3") (pinfunction "3_3") (pintype "passive"))
      (node (ref "JP29") (pin "3") (pinfunction "3_3") (pintype "passive"))
      (node (ref "JP30") (pin "3") (pinfunction "3_3") (pintype "passive"))
      (node (ref "JP31") (pin "3") (pinfunction "3_3") (pintype "passive"))
      (node (ref "JP32") (pin "3") (pinfunction "3_3") (pintype "passive"))
      (node (ref "JP33") (pin "3") (pinfunction "3_3") (pintype "passive"))
      (node (ref "JP34") (pin "3") (pinfunction "3_3") (pintype "passive"))
      (node (ref "JP35") (pin "3") (pinfunction "3_3") (pintype "passive"))
      (node (ref "JP38") (pin "3") (pinfunction "3_3") (pintype "passive"))
      (node (ref "JP39") (pin "3") (pinfunction "3_3") (pintype "passive"))
      (node (ref "JP4") (pin "1") (pinfunction "1_1") (pintype "passive"))
      (node (ref "JP40") (pin "3") (pinfunction "3_3") (pintype "passive"))
      (node (ref "JP41") (pin "3") (pinfunction "3_3") (pintype "passive"))
      (node (ref "JP42") (pin "3") (pinfunction "3_3") (pintype "passive"))
      (node (ref "JP43") (pin "1") (pinfunction "1_1") (pintype "passive"))
      (node (ref "JP43") (pin "3") (pinfunction "3_3") (pintype "passive"))
      (node (ref "JP44") (pin "3") (pinfunction "3_3") (pintype "passive"))
      (node (ref "JP45") (pin "3") (pinfunction "3_3") (pintype "passive"))
      (node (ref "JP46") (pin "3") (pinfunction "3_3") (pintype "passive"))
      (node (ref "JP47") (pin "3") (pinfunction "3_3") (pintype "passive"))
      (node (ref "JP48") (pin "3") (pinfunction "3_3") (pintype "passive"))
      (node (ref "JP49") (pin "3") (pinfunction "3_3") (pintype "passive"))
      (node (ref "JP5") (pin "1") (pinfunction "1_1") (pintype "passive"))
      (node (ref "JP50") (pin "3") (pinfunction "3_3") (pintype "passive"))
      (node (ref "JP51") (pin "3") (pinfunction "3_3") (pintype "passive"))
      (node (ref "JP52") (pin "3") (pinfunction "3_3") (pintype "passive"))
      (node (ref "JP53") (pin "3") (pinfunction "3_3") (pintype "passive"))
      (node (ref "JP54") (pin "3") (pinfunction "3_3") (pintype "passive"))
      (node (ref "JP55") (pin "3") (pinfunction "3_3") (pintype "passive"))
      (node (ref "JP56") (pin "3") (pinfunction "3_3") (pintype "passive"))
      (node (ref "JP57") (pin "3") (pinfunction "3_3") (pintype "passive"))
      (node (ref "JP6") (pin "1") (pinfunction "1_1") (pintype "passive"))
      (node (ref "JP7") (pin "3") (pinfunction "3_3") (pintype "passive"))
      (node (ref "JP8") (pin "1") (pinfunction "1_1") (pintype "passive"))
      (node (ref "JP9") (pin "3") (pinfunction "3_3") (pintype "passive"))
      (node (ref "R13") (pin "P$1") (pinfunction "1_P$1") (pintype "passive"))
      (node (ref "R14") (pin "P$1") (pinfunction "1_P$1") (pintype "passive"))
      (node (ref "R15") (pin "P$1") (pinfunction "1_P$1") (pintype "passive"))
      (node (ref "U1") (pin "2") (pinfunction "GND_2") (pintype "bidirectional"))
      (node (ref "U1") (pin "28") (pinfunction "GND_28") (pintype "bidirectional"))
      (node (ref "U1") (pin "29") (pinfunction "GND_29") (pintype "bidirectional"))
      (node (ref "U1") (pin "41") (pinfunction "GND_41") (pintype "bidirectional"))
      (node (ref "U1") (pin "55") (pinfunction "GND_55") (pintype "bidirectional"))
      (node (ref "U2") (pin "2") (pinfunction "GND_2") (pintype "bidirectional"))
      (node (ref "U2") (pin "37") (pinfunction "GND_37") (pintype "bidirectional"))
      (node (ref "U2") (pin "39") (pinfunction "GND_39") (pintype "bidirectional"))
      (node (ref "U3") (pin "GND") (pinfunction "GND_GND") (pintype "input"))
      (node (ref "X1") (pin "1") (pinfunction "1_1") (pintype "power_in"))
      (node (ref "X1") (pin "3") (pinfunction "3_3") (pintype "power_in"))
    )
    (net (code "58") (name "Net-(JP3-Pad1)") (class "Default")
      (node (ref "JP3") (pin "1") (pinfunction "1_1") (pintype "passive"))
      (node (ref "U3") (pin "OUT") (pinfunction "OUT_OUT") (pintype "output"))
    )
    (net (code "59") (name "VIN") (class "Default")
      (node (ref "C4") (pin "1") (pinfunction "+_1") (pintype "passive"))
      (node (ref "C6") (pin "1") (pinfunction "+_1") (pintype "passive"))
      (node (ref "IC2") (pin "8") (pinfunction "VCC2_8") (pintype "power_in"))
      (node (ref "IC3") (pin "8") (pinfunction "VCC2_8") (pintype "power_in"))
      (node (ref "JP3") (pin "3") (pinfunction "3_3") (pintype "passive"))
      (node (ref "JP4") (pin "2") (pinfunction "2_2") (pintype "passive"))
      (node (ref "U3") (pin "IN") (pinfunction "IN_IN") (pintype "input"))
      (node (ref "X1") (pin "2") (pinfunction "2_2") (pintype "power_in"))
    )
    (net (code "60") (name "unconnected-(JP8-Pad2)") (class "Default")
      (node (ref "JP8") (pin "2") (pinfunction "2_2") (pintype "passive"))
    )
    (net (code "61") (name "unconnected-(JP8-Pad3)") (class "Default")
      (node (ref "JP8") (pin "3") (pinfunction "3_3") (pintype "passive"))
    )
    (net (code "62") (name "unconnected-(JP8-Pad6)") (class "Default")
      (node (ref "JP8") (pin "6") (pinfunction "6_6") (pintype "passive"))
    )
    (net (code "63") (name "unconnected-(R15-2-PadP$2)") (class "Default")
      (node (ref "R15") (pin "P$2") (pinfunction "2_P$2") (pintype "passive"))
    )
    (net (code "64") (name "unconnected-(R15-3-PadP$3)") (class "Default")
      (node (ref "R15") (pin "P$3") (pinfunction "3_P$3") (pintype "passive"))
    )
    (net (code "65") (name "unconnected-(R15-4-PadP$4)") (class "Default")
      (node (ref "R15") (pin "P$4") (pinfunction "4_P$4") (pintype "passive"))
    )
    (net (code "66") (name "unconnected-(U1-5V_OUT-Pad1)") (class "Default")
      (node (ref "U1") (pin "1") (pinfunction "5V_OUT_1") (pintype "bidirectional"))
    )
    (net (code "67") (name "unconnected-(U2-5V_OUT-Pad1)") (class "Default")
      (node (ref "U2") (pin "1") (pinfunction "5V_OUT_1") (pintype "bidirectional"))
    )
  )
)
